# MV-LED.net
KiCad netlist of a schematic drawn in Altium Designer
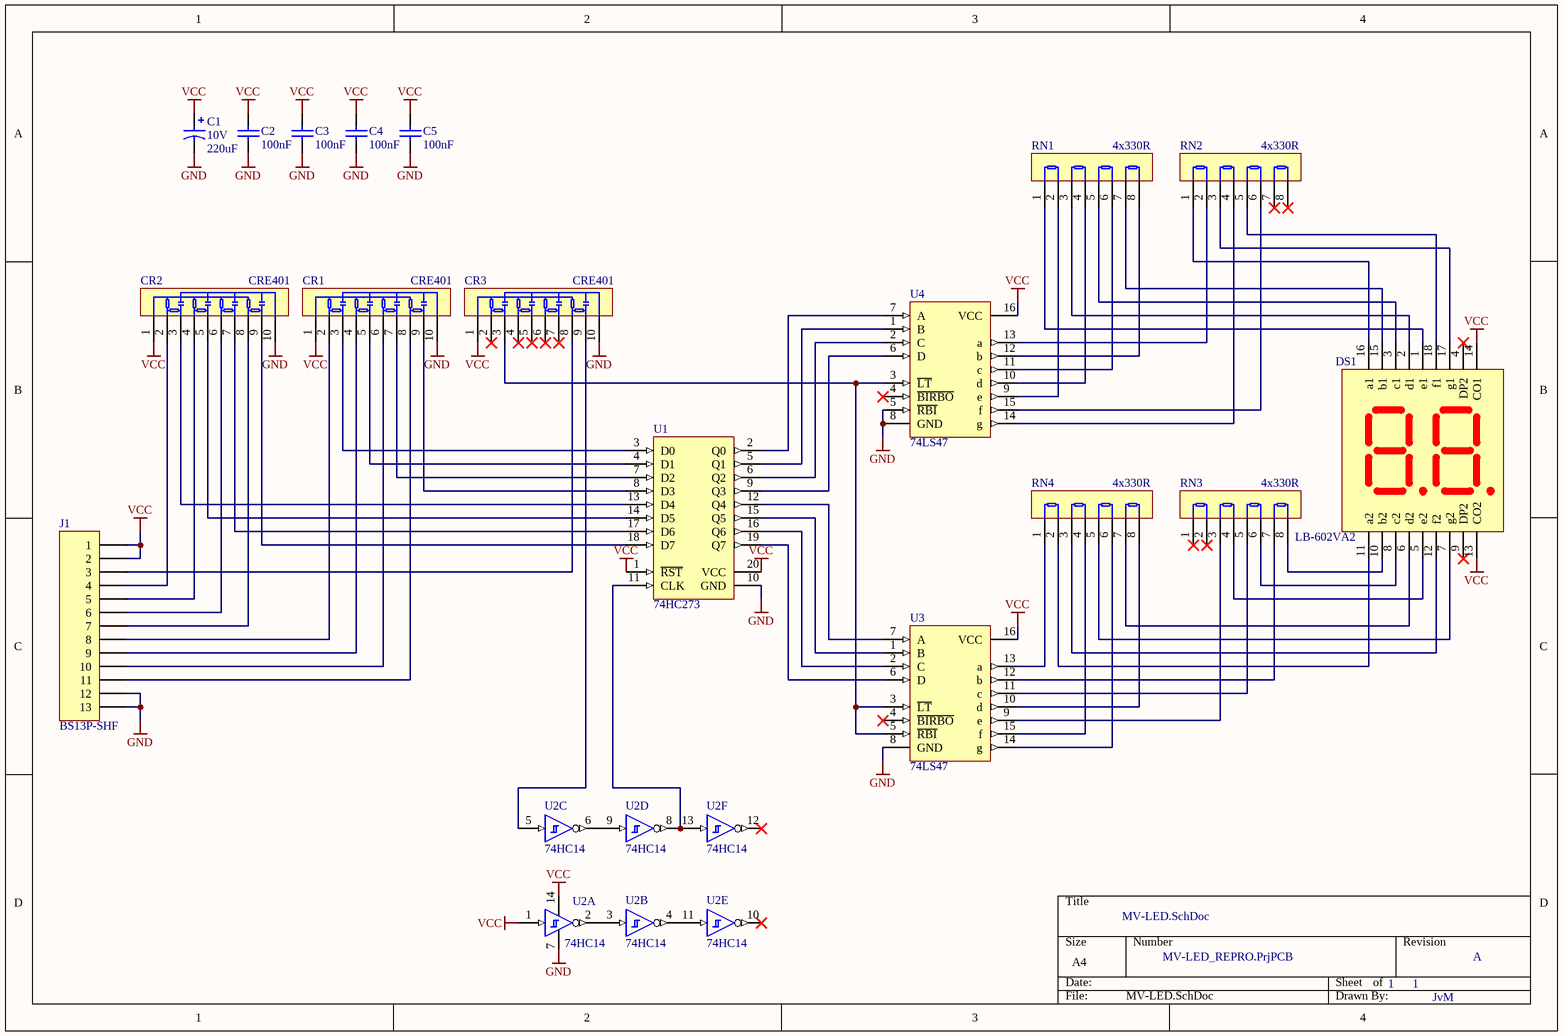
[diagram p0: MV-LED.SchDoc]

(export (version "E")
  (design (tool "Eeschema 10.0.6"))
  (components
    (comp (ref "C1")
      (value "220uF")
      (footprint "CapPol3.8_RA")
      (description "Polarized Capacitor, 3.8mm Pitch, 8mm Width")
      (fields (field (name "VOLTAGE") "10V") (field (name "Comment") "CapPol3.8"))
      (libsource (lib "MV-LED") (part "CapPol3.8"))
    )
    (comp (ref "C2")
      (value "100nF")
      (footprint "CapCer0.2")
      (description "Capacitor (THT), Ceramic, 5,08mm Pitch")
      (fields (field (name "VOLTAGE") "50V") (field (name "Comment") "CapCer0.2"))
      (libsource (lib "MV-LED") (part "CapCer0.2"))
    )
    (comp (ref "C3")
      (value "100nF")
      (footprint "CapCer0.2")
      (description "Capacitor (THT), Ceramic, 5,08mm Pitch")
      (fields (field (name "VOLTAGE") "50V") (field (name "Comment") "CapCer0.2"))
      (libsource (lib "MV-LED") (part "CapCer0.2"))
    )
    (comp (ref "C4")
      (value "100nF")
      (footprint "CapCer0.2")
      (description "Capacitor (THT), Ceramic, 5,08mm Pitch")
      (fields (field (name "VOLTAGE") "50V") (field (name "Comment") "CapCer0.2"))
      (libsource (lib "MV-LED") (part "CapCer0.2"))
    )
    (comp (ref "C5")
      (value "100nF")
      (footprint "CapCer0.2")
      (description "Capacitor (THT), Ceramic, 5,08mm Pitch")
      (fields (field (name "VOLTAGE") "50V") (field (name "Comment") "CapCer0.2"))
      (libsource (lib "MV-LED") (part "CapCer0.2"))
    )
    (comp (ref "CR1")
      (value "CRE401")
      (footprint "SIP10")
      (description "RRC Array")
      (libsource (lib "MV-LED") (part "CRE401"))
    )
    (comp (ref "CR2")
      (value "CRE401")
      (footprint "SIP10")
      (description "RRC Array")
      (libsource (lib "MV-LED") (part "CRE401"))
    )
    (comp (ref "CR3")
      (value "CRE401")
      (footprint "SIP10")
      (description "RRC Array")
      (libsource (lib "MV-LED") (part "CRE401"))
    )
    (comp (ref "DS1")
      (value "LB-602VA2")
      (footprint "LB-602VA2")
      (description "Double Digits LED Numeric Display")
      (libsource (lib "MV-LED") (part "LB-602VA2"))
    )
    (comp (ref "J1")
      (value "BS13P-SHF")
      (footprint "JST BS13P-SHF-1AA")
      (description "JST HVQ Series, 2.5mm Pitch 13 Way 1 Row Right Angle PCB Header THT")
      (libsource (lib "MV-LED") (part "JST BS13P-SHF-1AA"))
    )
    (comp (ref "RN1")
      (value "4x330R")
      (footprint "SIP8")
      (description "Parallel Resistor Network 4x330R")
      (libsource (lib "MV-LED") (part "SIL8_4RES_330R"))
    )
    (comp (ref "RN2")
      (value "4x330R")
      (footprint "SIP8")
      (description "Parallel Resistor Network 4x330R")
      (libsource (lib "MV-LED") (part "SIL8_4RES_330R"))
    )
    (comp (ref "RN3")
      (value "4x330R")
      (footprint "SIP8")
      (description "Parallel Resistor Network 4x330R")
      (libsource (lib "MV-LED") (part "SIL8_4RES_330R"))
    )
    (comp (ref "RN4")
      (value "4x330R")
      (footprint "SIP8")
      (description "Parallel Resistor Network 4x330R")
      (libsource (lib "MV-LED") (part "SIL8_4RES_330R"))
    )
    (comp (ref "U1")
      (value "74HC273")
      (footprint "DIP20")
      (description "Octal D Type FLIP-FLOP with Clear,")
      (libsource (lib "MV-LED") (part "74HC273"))
    )
    (comp (ref "U2")
      (value "74HC14")
      (footprint "DIP14")
      (description "Hex Schmitt-Trigger Inverters")
      (libsource (lib "MV-LED") (part "74HC14"))
    )
    (comp (ref "U3")
      (value "74LS47")
      (footprint "DIP16")
      (description "BCD-to-Seven-Segment Decoder/Driver")
      (libsource (lib "MV-LED") (part "74LS47"))
    )
    (comp (ref "U4")
      (value "74LS47")
      (footprint "DIP16")
      (description "BCD-to-Seven-Segment Decoder/Driver")
      (libsource (lib "MV-LED") (part "74LS47"))
    )
  )
  (nets
    (net (code "1") (name "GND") (class "Default")
      (node (ref "C1") (pin "2") (pinfunction "2_2") (pintype "passive"))
      (node (ref "C2") (pin "2") (pinfunction "2_2") (pintype "passive"))
      (node (ref "C3") (pin "2") (pinfunction "2_2") (pintype "passive"))
      (node (ref "C4") (pin "2") (pinfunction "2_2") (pintype "passive"))
      (node (ref "C5") (pin "2") (pinfunction "2_2") (pintype "passive"))
      (node (ref "CR1") (pin "10") (pinfunction "10_10") (pintype "passive"))
      (node (ref "CR2") (pin "10") (pinfunction "10_10") (pintype "passive"))
      (node (ref "CR3") (pin "10") (pinfunction "10_10") (pintype "passive"))
      (node (ref "J1") (pin "12") (pinfunction "12_12") (pintype "passive"))
      (node (ref "J1") (pin "13") (pinfunction "13_13") (pintype "passive"))
      (node (ref "U1") (pin "10") (pinfunction "GND_10") (pintype "power_in"))
      (node (ref "U2") (pin "7") (pinfunction "GND_7") (pintype "power_in"))
      (node (ref "U3") (pin "8") (pinfunction "GND_8") (pintype "power_in"))
      (node (ref "U4") (pin "5") (pinfunction "~{RBI}_5") (pintype "input"))
      (node (ref "U4") (pin "8") (pinfunction "GND_8") (pintype "power_in"))
    )
    (net (code "2") (name "Net-(CR1-Pad2)") (class "Default")
      (node (ref "CR1") (pin "2") (pinfunction "2_2") (pintype "passive"))
      (node (ref "J1") (pin "8") (pinfunction "8_8") (pintype "passive"))
    )
    (net (code "3") (name "Net-(CR1-Pad4)") (class "Default")
      (node (ref "CR1") (pin "4") (pinfunction "4_4") (pintype "passive"))
      (node (ref "J1") (pin "9") (pinfunction "9_9") (pintype "passive"))
    )
    (net (code "4") (name "Net-(CR1-Pad6)") (class "Default")
      (node (ref "CR1") (pin "6") (pinfunction "6_6") (pintype "passive"))
      (node (ref "J1") (pin "10") (pinfunction "10_10") (pintype "passive"))
    )
    (net (code "5") (name "Net-(CR1-Pad8)") (class "Default")
      (node (ref "CR1") (pin "8") (pinfunction "8_8") (pintype "passive"))
      (node (ref "J1") (pin "11") (pinfunction "11_11") (pintype "passive"))
    )
    (net (code "6") (name "Net-(CR2-Pad2)") (class "Default")
      (node (ref "CR2") (pin "2") (pinfunction "2_2") (pintype "passive"))
      (node (ref "J1") (pin "4") (pinfunction "4_4") (pintype "passive"))
    )
    (net (code "7") (name "Net-(CR2-Pad4)") (class "Default")
      (node (ref "CR2") (pin "4") (pinfunction "4_4") (pintype "passive"))
      (node (ref "J1") (pin "5") (pinfunction "5_5") (pintype "passive"))
    )
    (net (code "8") (name "Net-(CR2-Pad6)") (class "Default")
      (node (ref "CR2") (pin "6") (pinfunction "6_6") (pintype "passive"))
      (node (ref "J1") (pin "6") (pinfunction "6_6") (pintype "passive"))
    )
    (net (code "9") (name "Net-(CR2-Pad8)") (class "Default")
      (node (ref "CR2") (pin "8") (pinfunction "8_8") (pintype "passive"))
      (node (ref "J1") (pin "7") (pinfunction "7_7") (pintype "passive"))
    )
    (net (code "10") (name "Net-(CR3-Pad8)") (class "Default")
      (node (ref "CR3") (pin "8") (pinfunction "8_8") (pintype "passive"))
      (node (ref "J1") (pin "3") (pinfunction "3_3") (pintype "passive"))
    )
    (net (code "11") (name "Net-(DS1-a1)") (class "Default")
      (node (ref "DS1") (pin "16") (pinfunction "a1_16") (pintype "passive"))
      (node (ref "RN2") (pin "1") (pinfunction "1_1") (pintype "passive"))
    )
    (net (code "12") (name "Net-(DS1-a2)") (class "Default")
      (node (ref "DS1") (pin "11") (pinfunction "a2_11") (pintype "passive"))
      (node (ref "RN4") (pin "2") (pinfunction "2_2") (pintype "passive"))
    )
    (net (code "13") (name "Net-(DS1-b1)") (class "Default")
      (node (ref "DS1") (pin "15") (pinfunction "b1_15") (pintype "passive"))
      (node (ref "RN1") (pin "7") (pinfunction "7_7") (pintype "passive"))
    )
    (net (code "14") (name "Net-(DS1-b2)") (class "Default")
      (node (ref "DS1") (pin "10") (pinfunction "b2_10") (pintype "passive"))
      (node (ref "RN3") (pin "8") (pinfunction "8_8") (pintype "passive"))
    )
    (net (code "15") (name "Net-(DS1-c1)") (class "Default")
      (node (ref "DS1") (pin "3") (pinfunction "c1_3") (pintype "passive"))
      (node (ref "RN1") (pin "5") (pinfunction "5_5") (pintype "passive"))
    )
    (net (code "16") (name "Net-(DS1-c2)") (class "Default")
      (node (ref "DS1") (pin "8") (pinfunction "c2_8") (pintype "passive"))
      (node (ref "RN3") (pin "6") (pinfunction "6_6") (pintype "passive"))
    )
    (net (code "17") (name "Net-(DS1-d1)") (class "Default")
      (node (ref "DS1") (pin "2") (pinfunction "d1_2") (pintype "passive"))
      (node (ref "RN1") (pin "3") (pinfunction "3_3") (pintype "passive"))
    )
    (net (code "18") (name "Net-(DS1-d2)") (class "Default")
      (node (ref "DS1") (pin "6") (pinfunction "d2_6") (pintype "passive"))
      (node (ref "RN4") (pin "7") (pinfunction "7_7") (pintype "passive"))
    )
    (net (code "19") (name "Net-(DS1-e1)") (class "Default")
      (node (ref "DS1") (pin "1") (pinfunction "e1_1") (pintype "passive"))
      (node (ref "RN1") (pin "1") (pinfunction "1_1") (pintype "passive"))
    )
    (net (code "20") (name "Net-(DS1-e2)") (class "Default")
      (node (ref "DS1") (pin "5") (pinfunction "e2_5") (pintype "passive"))
      (node (ref "RN3") (pin "4") (pinfunction "4_4") (pintype "passive"))
    )
    (net (code "21") (name "Net-(DS1-f1)") (class "Default")
      (node (ref "DS1") (pin "18") (pinfunction "f1_18") (pintype "passive"))
      (node (ref "RN2") (pin "5") (pinfunction "5_5") (pintype "passive"))
    )
    (net (code "22") (name "Net-(DS1-f2)") (class "Default")
      (node (ref "DS1") (pin "12") (pinfunction "f2_12") (pintype "passive"))
      (node (ref "RN4") (pin "3") (pinfunction "3_3") (pintype "passive"))
    )
    (net (code "23") (name "Net-(DS1-g1)") (class "Default")
      (node (ref "DS1") (pin "17") (pinfunction "g1_17") (pintype "passive"))
      (node (ref "RN2") (pin "3") (pinfunction "3_3") (pintype "passive"))
    )
    (net (code "24") (name "Net-(DS1-g2)") (class "Default")
      (node (ref "DS1") (pin "7") (pinfunction "g2_7") (pintype "passive"))
      (node (ref "RN4") (pin "5") (pinfunction "5_5") (pintype "passive"))
    )
    (net (code "25") (name "Net-(U1-CLK)") (class "Default")
      (node (ref "U1") (pin "11") (pinfunction "CLK_11") (pintype "input"))
      (node (ref "U2") (pin "13") (pinfunction "6A_13") (pintype "input"))
      (node (ref "U2") (pin "8") (pinfunction "4Y_8") (pintype "output"))
    )
    (net (code "26") (name "Net-(U1-D0)") (class "Default")
      (node (ref "CR1") (pin "3") (pinfunction "3_3") (pintype "passive"))
      (node (ref "U1") (pin "3") (pinfunction "D0_3") (pintype "input"))
    )
    (net (code "27") (name "Net-(U1-D1)") (class "Default")
      (node (ref "CR1") (pin "5") (pinfunction "5_5") (pintype "passive"))
      (node (ref "U1") (pin "4") (pinfunction "D1_4") (pintype "input"))
    )
    (net (code "28") (name "Net-(U1-D2)") (class "Default")
      (node (ref "CR1") (pin "7") (pinfunction "7_7") (pintype "passive"))
      (node (ref "U1") (pin "7") (pinfunction "D2_7") (pintype "input"))
    )
    (net (code "29") (name "Net-(U1-D3)") (class "Default")
      (node (ref "CR1") (pin "9") (pinfunction "9_9") (pintype "passive"))
      (node (ref "U1") (pin "8") (pinfunction "D3_8") (pintype "input"))
    )
    (net (code "30") (name "Net-(U1-D4)") (class "Default")
      (node (ref "CR2") (pin "3") (pinfunction "3_3") (pintype "passive"))
      (node (ref "U1") (pin "13") (pinfunction "D4_13") (pintype "input"))
    )
    (net (code "31") (name "Net-(U1-D5)") (class "Default")
      (node (ref "CR2") (pin "5") (pinfunction "5_5") (pintype "passive"))
      (node (ref "U1") (pin "14") (pinfunction "D5_14") (pintype "input"))
    )
    (net (code "32") (name "Net-(U1-D6)") (class "Default")
      (node (ref "CR2") (pin "7") (pinfunction "7_7") (pintype "passive"))
      (node (ref "U1") (pin "17") (pinfunction "D6_17") (pintype "input"))
    )
    (net (code "33") (name "Net-(U1-D7)") (class "Default")
      (node (ref "CR2") (pin "9") (pinfunction "9_9") (pintype "passive"))
      (node (ref "U1") (pin "18") (pinfunction "D7_18") (pintype "input"))
    )
    (net (code "34") (name "Net-(U1-Q0)") (class "Default")
      (node (ref "U1") (pin "2") (pinfunction "Q0_2") (pintype "output"))
      (node (ref "U4") (pin "7") (pinfunction "A_7") (pintype "input"))
    )
    (net (code "35") (name "Net-(U1-Q1)") (class "Default")
      (node (ref "U1") (pin "5") (pinfunction "Q1_5") (pintype "output"))
      (node (ref "U4") (pin "1") (pinfunction "B_1") (pintype "input"))
    )
    (net (code "36") (name "Net-(U1-Q2)") (class "Default")
      (node (ref "U1") (pin "6") (pinfunction "Q2_6") (pintype "output"))
      (node (ref "U4") (pin "2") (pinfunction "C_2") (pintype "input"))
    )
    (net (code "37") (name "Net-(U1-Q3)") (class "Default")
      (node (ref "U1") (pin "9") (pinfunction "Q3_9") (pintype "output"))
      (node (ref "U4") (pin "6") (pinfunction "D_6") (pintype "input"))
    )
    (net (code "38") (name "Net-(U1-Q4)") (class "Default")
      (node (ref "U1") (pin "12") (pinfunction "Q4_12") (pintype "output"))
      (node (ref "U3") (pin "7") (pinfunction "A_7") (pintype "input"))
    )
    (net (code "39") (name "Net-(U1-Q5)") (class "Default")
      (node (ref "U1") (pin "15") (pinfunction "Q5_15") (pintype "output"))
      (node (ref "U3") (pin "1") (pinfunction "B_1") (pintype "input"))
    )
    (net (code "40") (name "Net-(U1-Q6)") (class "Default")
      (node (ref "U1") (pin "16") (pinfunction "Q6_16") (pintype "output"))
      (node (ref "U3") (pin "2") (pinfunction "C_2") (pintype "input"))
    )
    (net (code "41") (name "Net-(U1-Q7)") (class "Default")
      (node (ref "U1") (pin "19") (pinfunction "Q7_19") (pintype "output"))
      (node (ref "U3") (pin "6") (pinfunction "D_6") (pintype "input"))
    )
    (net (code "42") (name "Net-(U2A-1Y)") (class "Default")
      (node (ref "U2") (pin "2") (pinfunction "1Y_2") (pintype "output"))
      (node (ref "U2") (pin "3") (pinfunction "2A_3") (pintype "input"))
    )
    (net (code "43") (name "Net-(U2B-2Y)") (class "Default")
      (node (ref "U2") (pin "11") (pinfunction "5A_11") (pintype "input"))
      (node (ref "U2") (pin "4") (pinfunction "2Y_4") (pintype "output"))
    )
    (net (code "44") (name "Net-(U2C-3A)") (class "Default")
      (node (ref "CR3") (pin "9") (pinfunction "9_9") (pintype "passive"))
      (node (ref "U2") (pin "5") (pinfunction "3A_5") (pintype "input"))
    )
    (net (code "45") (name "Net-(U2C-3Y)") (class "Default")
      (node (ref "U2") (pin "6") (pinfunction "3Y_6") (pintype "output"))
      (node (ref "U2") (pin "9") (pinfunction "4A_9") (pintype "input"))
    )
    (net (code "46") (name "Net-(U3-a)") (class "Default")
      (node (ref "RN4") (pin "1") (pinfunction "1_1") (pintype "passive"))
      (node (ref "U3") (pin "13") (pinfunction "a_13") (pintype "output"))
    )
    (net (code "47") (name "Net-(U3-b)") (class "Default")
      (node (ref "RN3") (pin "7") (pinfunction "7_7") (pintype "passive"))
      (node (ref "U3") (pin "12") (pinfunction "b_12") (pintype "output"))
    )
    (net (code "48") (name "Net-(U3-c)") (class "Default")
      (node (ref "RN3") (pin "5") (pinfunction "5_5") (pintype "passive"))
      (node (ref "U3") (pin "11") (pinfunction "c_11") (pintype "output"))
    )
    (net (code "49") (name "Net-(U3-d)") (class "Default")
      (node (ref "RN4") (pin "8") (pinfunction "8_8") (pintype "passive"))
      (node (ref "U3") (pin "10") (pinfunction "d_10") (pintype "output"))
    )
    (net (code "50") (name "Net-(U3-e)") (class "Default")
      (node (ref "RN3") (pin "3") (pinfunction "3_3") (pintype "passive"))
      (node (ref "U3") (pin "9") (pinfunction "e_9") (pintype "output"))
    )
    (net (code "51") (name "Net-(U3-f)") (class "Default")
      (node (ref "RN4") (pin "4") (pinfunction "4_4") (pintype "passive"))
      (node (ref "U3") (pin "15") (pinfunction "f_15") (pintype "output"))
    )
    (net (code "52") (name "Net-(U3-g)") (class "Default")
      (node (ref "RN4") (pin "6") (pinfunction "6_6") (pintype "passive"))
      (node (ref "U3") (pin "14") (pinfunction "g_14") (pintype "output"))
    )
    (net (code "53") (name "Net-(U3-~{LT})") (class "Default")
      (node (ref "CR3") (pin "3") (pinfunction "3_3") (pintype "passive"))
      (node (ref "U3") (pin "3") (pinfunction "~{LT}_3") (pintype "input"))
      (node (ref "U3") (pin "5") (pinfunction "~{RBI}_5") (pintype "input"))
      (node (ref "U4") (pin "3") (pinfunction "~{LT}_3") (pintype "input"))
    )
    (net (code "54") (name "Net-(U4-a)") (class "Default")
      (node (ref "RN2") (pin "2") (pinfunction "2_2") (pintype "passive"))
      (node (ref "U4") (pin "13") (pinfunction "a_13") (pintype "output"))
    )
    (net (code "55") (name "Net-(U4-b)") (class "Default")
      (node (ref "RN1") (pin "8") (pinfunction "8_8") (pintype "passive"))
      (node (ref "U4") (pin "12") (pinfunction "b_12") (pintype "output"))
    )
    (net (code "56") (name "Net-(U4-c)") (class "Default")
      (node (ref "RN1") (pin "6") (pinfunction "6_6") (pintype "passive"))
      (node (ref "U4") (pin "11") (pinfunction "c_11") (pintype "output"))
    )
    (net (code "57") (name "Net-(U4-d)") (class "Default")
      (node (ref "RN1") (pin "4") (pinfunction "4_4") (pintype "passive"))
      (node (ref "U4") (pin "10") (pinfunction "d_10") (pintype "output"))
    )
    (net (code "58") (name "Net-(U4-e)") (class "Default")
      (node (ref "RN1") (pin "2") (pinfunction "2_2") (pintype "passive"))
      (node (ref "U4") (pin "9") (pinfunction "e_9") (pintype "output"))
    )
    (net (code "59") (name "Net-(U4-f)") (class "Default")
      (node (ref "RN2") (pin "6") (pinfunction "6_6") (pintype "passive"))
      (node (ref "U4") (pin "15") (pinfunction "f_15") (pintype "output"))
    )
    (net (code "60") (name "Net-(U4-g)") (class "Default")
      (node (ref "RN2") (pin "4") (pinfunction "4_4") (pintype "passive"))
      (node (ref "U4") (pin "14") (pinfunction "g_14") (pintype "output"))
    )
    (net (code "61") (name "VCC") (class "Default")
      (node (ref "C1") (pin "1") (pinfunction "1_1") (pintype "passive"))
      (node (ref "C2") (pin "1") (pinfunction "1_1") (pintype "passive"))
      (node (ref "C3") (pin "1") (pinfunction "1_1") (pintype "passive"))
      (node (ref "C4") (pin "1") (pinfunction "1_1") (pintype "passive"))
      (node (ref "C5") (pin "1") (pinfunction "1_1") (pintype "passive"))
      (node (ref "CR1") (pin "1") (pinfunction "1_1") (pintype "passive"))
      (node (ref "CR2") (pin "1") (pinfunction "1_1") (pintype "passive"))
      (node (ref "CR3") (pin "1") (pinfunction "1_1") (pintype "passive"))
      (node (ref "DS1") (pin "13") (pinfunction "CO2_13") (pintype "passive"))
      (node (ref "DS1") (pin "14") (pinfunction "CO1_14") (pintype "passive"))
      (node (ref "J1") (pin "1") (pinfunction "1_1") (pintype "passive"))
      (node (ref "J1") (pin "2") (pinfunction "2_2") (pintype "passive"))
      (node (ref "U1") (pin "1") (pinfunction "~{RST}_1") (pintype "input"))
      (node (ref "U1") (pin "20") (pinfunction "VCC_20") (pintype "power_in"))
      (node (ref "U2") (pin "1") (pinfunction "1A_1") (pintype "input"))
      (node (ref "U2") (pin "14") (pinfunction "VCC_14") (pintype "power_in"))
      (node (ref "U3") (pin "16") (pinfunction "VCC_16") (pintype "power_in"))
      (node (ref "U4") (pin "16") (pinfunction "VCC_16") (pintype "power_in"))
    )
    (net (code "62") (name "unconnected-(CR3-Pad2)") (class "Default")
      (node (ref "CR3") (pin "2") (pinfunction "2_2") (pintype "passive+no_connect"))
    )
    (net (code "63") (name "unconnected-(CR3-Pad4)") (class "Default")
      (node (ref "CR3") (pin "4") (pinfunction "4_4") (pintype "passive+no_connect"))
    )
    (net (code "64") (name "unconnected-(CR3-Pad5)") (class "Default")
      (node (ref "CR3") (pin "5") (pinfunction "5_5") (pintype "passive+no_connect"))
    )
    (net (code "65") (name "unconnected-(CR3-Pad6)") (class "Default")
      (node (ref "CR3") (pin "6") (pinfunction "6_6") (pintype "passive+no_connect"))
    )
    (net (code "66") (name "unconnected-(CR3-Pad7)") (class "Default")
      (node (ref "CR3") (pin "7") (pinfunction "7_7") (pintype "passive+no_connect"))
    )
    (net (code "67") (name "unconnected-(DS1-DP2-Pad4)") (class "Default")
      (node (ref "DS1") (pin "4") (pinfunction "DP2_4") (pintype "passive+no_connect"))
    )
    (net (code "68") (name "unconnected-(DS1-DP2-Pad9)") (class "Default")
      (node (ref "DS1") (pin "9") (pinfunction "DP2_9") (pintype "passive+no_connect"))
    )
    (net (code "69") (name "unconnected-(RN2-Pad7)") (class "Default")
      (node (ref "RN2") (pin "7") (pinfunction "7_7") (pintype "passive+no_connect"))
    )
    (net (code "70") (name "unconnected-(RN2-Pad8)") (class "Default")
      (node (ref "RN2") (pin "8") (pinfunction "8_8") (pintype "passive+no_connect"))
    )
    (net (code "71") (name "unconnected-(RN3-Pad1)") (class "Default")
      (node (ref "RN3") (pin "1") (pinfunction "1_1") (pintype "passive+no_connect"))
    )
    (net (code "72") (name "unconnected-(RN3-Pad2)") (class "Default")
      (node (ref "RN3") (pin "2") (pinfunction "2_2") (pintype "passive+no_connect"))
    )
    (net (code "73") (name "unconnected-(U2E-5Y-Pad10)") (class "Default")
      (node (ref "U2") (pin "10") (pinfunction "5Y_10") (pintype "output+no_connect"))
    )
    (net (code "74") (name "unconnected-(U2F-6Y-Pad12)") (class "Default")
      (node (ref "U2") (pin "12") (pinfunction "6Y_12") (pintype "output+no_connect"))
    )
    (net (code "75") (name "unconnected-(U3-~{BIRBO}-Pad4)") (class "Default")
      (node (ref "U3") (pin "4") (pinfunction "~{BIRBO}_4") (pintype "input+no_connect"))
    )
    (net (code "76") (name "unconnected-(U4-~{BIRBO}-Pad4)") (class "Default")
      (node (ref "U4") (pin "4") (pinfunction "~{BIRBO}_4") (pintype "input+no_connect"))
    )
  )
)
